# Regulator.net
KiCad netlist of a schematic drawn in Altium Designer
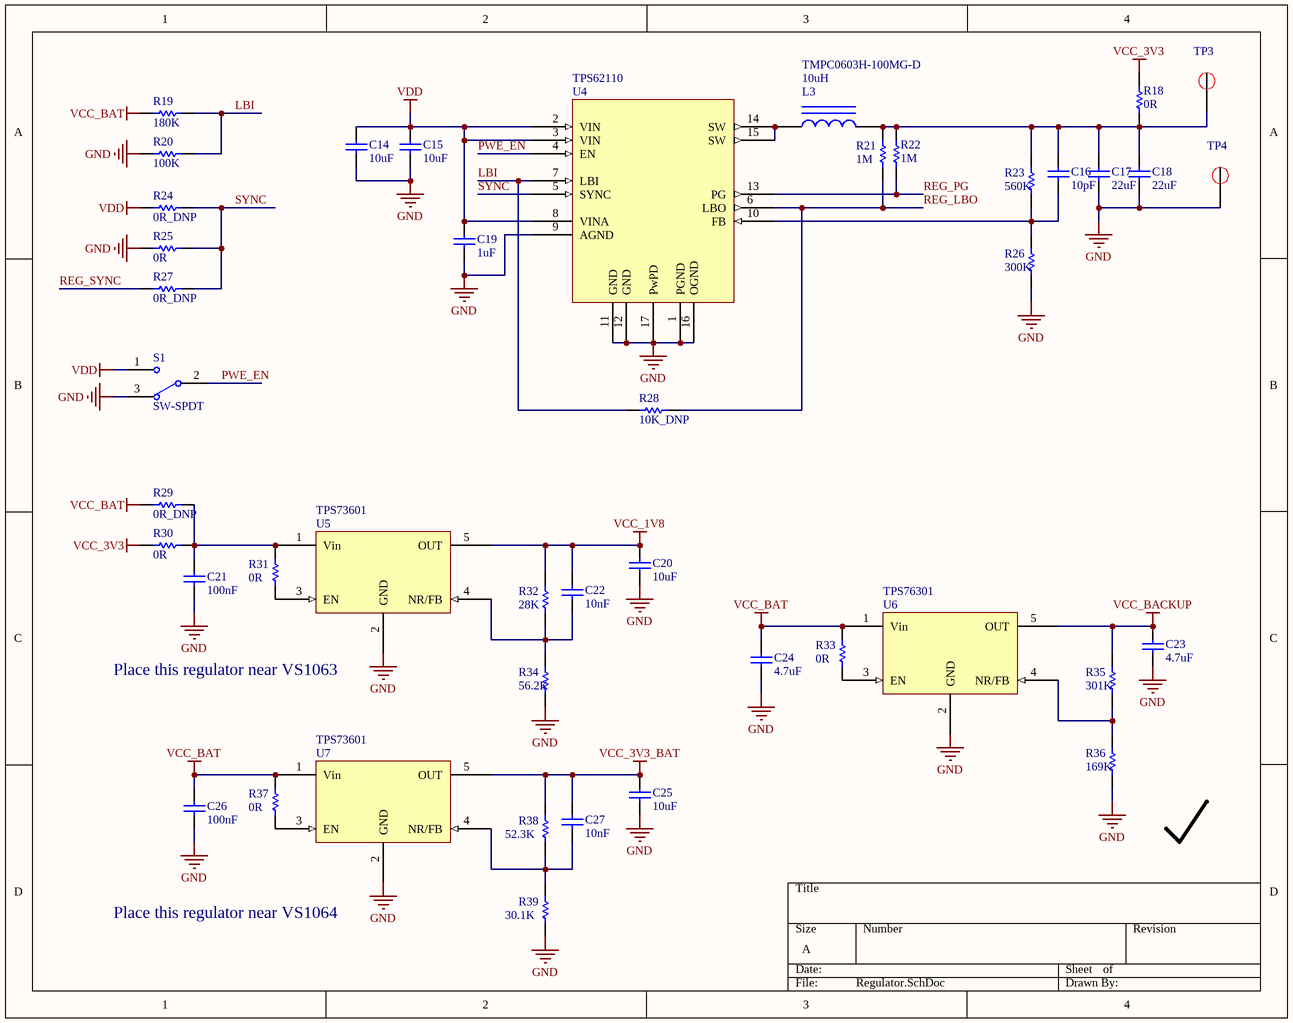
[diagram p0: Regulator.SchDoc]

(export (version "E")
  (design (tool "Eeschema 10.0.6"))
  (components
    (comp (ref "C14")
      (value "10uF")
      (footprint "C1206")
      (description "Capacitor (Semiconductor SIM Model)")
      (fields (field (name "Comment") "Cap Semi") (field (name "PUBLISHER") "Altium Limited"))
      (libsource (lib "Miscellaneous Devices") (part "Cap Semi"))
    )
    (comp (ref "C15")
      (value "10uF")
      (footprint "C1206")
      (description "Capacitor (Semiconductor SIM Model)")
      (fields (field (name "Comment") "Cap Semi") (field (name "PUBLISHER") "Altium Limited"))
      (libsource (lib "Miscellaneous Devices") (part "Cap Semi"))
    )
    (comp (ref "C16")
      (value "10pF")
      (footprint "0603PKG")
      (description "Capacitor (Semiconductor SIM Model)")
      (fields (field (name "Comment") "Cap Semi") (field (name "PUBLISHER") "Altium Limited"))
      (libsource (lib "Miscellaneous Devices") (part "Cap Semi"))
    )
    (comp (ref "C17")
      (value "22uF")
      (footprint "C1206")
      (description "Capacitor (Semiconductor SIM Model)")
      (fields (field (name "Comment") "Cap Semi") (field (name "PUBLISHER") "Altium Limited"))
      (libsource (lib "Miscellaneous Devices") (part "Cap Semi"))
    )
    (comp (ref "C18")
      (value "22uF")
      (footprint "C1206")
      (description "Capacitor (Semiconductor SIM Model)")
      (fields (field (name "Comment") "Cap Semi") (field (name "PUBLISHER") "Altium Limited"))
      (libsource (lib "Miscellaneous Devices") (part "Cap Semi"))
    )
    (comp (ref "C19")
      (value "1uF")
      (footprint "0603PKG")
      (description "Capacitor (Semiconductor SIM Model)")
      (fields (field (name "Comment") "Cap Semi") (field (name "PUBLISHER") "Altium Limited"))
      (libsource (lib "Miscellaneous Devices") (part "Cap Semi"))
    )
    (comp (ref "C20")
      (value "10uF")
      (footprint "0603PKG")
      (description "Capacitor (Semiconductor SIM Model)")
      (fields (field (name "Comment") "Cap Semi") (field (name "PUBLISHER") "Altium Limited"))
      (libsource (lib "Miscellaneous Devices") (part "Cap Semi"))
    )
    (comp (ref "C21")
      (value "100nF")
      (footprint "0603PKG")
      (description "Capacitor (Semiconductor SIM Model)")
      (fields (field (name "Comment") "Cap Semi") (field (name "PUBLISHER") "Altium Limited"))
      (libsource (lib "Miscellaneous Devices") (part "Cap Semi"))
    )
    (comp (ref "C22")
      (value "10nF")
      (footprint "0603PKG")
      (description "Capacitor (Semiconductor SIM Model)")
      (fields (field (name "Comment") "Cap Semi") (field (name "PUBLISHER") "Altium Limited"))
      (libsource (lib "Miscellaneous Devices") (part "Cap Semi"))
    )
    (comp (ref "C23")
      (value "4.7uF")
      (footprint "C0805")
      (description "Capacitor (Semiconductor SIM Model)")
      (fields (field (name "Comment") "Cap Semi") (field (name "PUBLISHER") "Altium Limited"))
      (libsource (lib "Miscellaneous Devices") (part "Cap Semi"))
    )
    (comp (ref "C24")
      (value "4.7uF")
      (footprint "C0805")
      (description "Capacitor (Semiconductor SIM Model)")
      (fields (field (name "Comment") "Cap Semi") (field (name "PUBLISHER") "Altium Limited"))
      (libsource (lib "Miscellaneous Devices") (part "Cap Semi"))
    )
    (comp (ref "C25")
      (value "10uF")
      (footprint "0603PKG")
      (description "Capacitor (Semiconductor SIM Model)")
      (fields (field (name "Comment") "Cap Semi") (field (name "PUBLISHER") "Altium Limited"))
      (libsource (lib "Miscellaneous Devices") (part "Cap Semi"))
    )
    (comp (ref "C26")
      (value "100nF")
      (footprint "0603PKG")
      (description "Capacitor (Semiconductor SIM Model)")
      (fields (field (name "Comment") "Cap Semi") (field (name "PUBLISHER") "Altium Limited"))
      (libsource (lib "Miscellaneous Devices") (part "Cap Semi"))
    )
    (comp (ref "C27")
      (value "10nF")
      (footprint "0603PKG")
      (description "Capacitor (Semiconductor SIM Model)")
      (fields (field (name "Comment") "Cap Semi") (field (name "PUBLISHER") "Altium Limited"))
      (libsource (lib "Miscellaneous Devices") (part "Cap Semi"))
    )
    (comp (ref "L3")
      (value "TMPC0603H-100MG-D")
      (footprint "CAPM3216X18N")
      (description "Magnetic-Core Inductor")
      (fields (field (name "ALTIUM_VALUE") "10uH") (field (name "PUBLISHER") "Altium Limited"))
      (libsource (lib "Miscellaneous Devices") (part "Inductor Iron"))
    )
    (comp (ref "R18")
      (value "0R")
      (footprint "C0805")
      (description "Resistor")
      (fields (field (name "Comment") "Res1") (field (name "PUBLISHER") "Altium Limited"))
      (libsource (lib "Miscellaneous Devices") (part "Res1"))
    )
    (comp (ref "R19")
      (value "180K")
      (footprint "0603PKG")
      (description "Resistor")
      (fields (field (name "Comment") "Res1") (field (name "PUBLISHER") "Altium Limited"))
      (libsource (lib "Miscellaneous Devices") (part "Res1"))
    )
    (comp (ref "R20")
      (value "100K")
      (footprint "0603PKG")
      (description "Resistor")
      (fields (field (name "Comment") "Res1") (field (name "PUBLISHER") "Altium Limited"))
      (libsource (lib "Miscellaneous Devices") (part "Res1"))
    )
    (comp (ref "R21")
      (value "1M")
      (footprint "0603PKG")
      (description "Resistor")
      (fields (field (name "Comment") "Res1") (field (name "PUBLISHER") "Altium Limited"))
      (libsource (lib "Miscellaneous Devices") (part "Res1"))
    )
    (comp (ref "R22")
      (value "1M")
      (footprint "0603PKG")
      (description "Resistor")
      (fields (field (name "Comment") "Res1") (field (name "PUBLISHER") "Altium Limited"))
      (libsource (lib "Miscellaneous Devices") (part "Res1"))
    )
    (comp (ref "R23")
      (value "560K")
      (footprint "0603PKG")
      (description "Resistor")
      (fields (field (name "Comment") "Res1") (field (name "PUBLISHER") "Altium Limited"))
      (libsource (lib "Miscellaneous Devices") (part "Res1"))
    )
    (comp (ref "R24")
      (value "0R_DNP")
      (footprint "0603PKG")
      (description "Resistor")
      (fields (field (name "Comment") "Res1") (field (name "PUBLISHER") "Altium Limited"))
      (libsource (lib "Miscellaneous Devices") (part "Res1"))
    )
    (comp (ref "R25")
      (value "0R")
      (footprint "0603PKG")
      (description "Resistor")
      (fields (field (name "Comment") "Res1") (field (name "PUBLISHER") "Altium Limited"))
      (libsource (lib "Miscellaneous Devices") (part "Res1"))
    )
    (comp (ref "R26")
      (value "300K")
      (footprint "0603PKG")
      (description "Resistor")
      (fields (field (name "Comment") "Res1") (field (name "PUBLISHER") "Altium Limited"))
      (libsource (lib "Miscellaneous Devices") (part "Res1"))
    )
    (comp (ref "R27")
      (value "0R_DNP")
      (footprint "0603PKG")
      (description "Resistor")
      (fields (field (name "Comment") "Res1") (field (name "PUBLISHER") "Altium Limited"))
      (libsource (lib "Miscellaneous Devices") (part "Res1"))
    )
    (comp (ref "R28")
      (value "10K_DNP")
      (footprint "0603PKG")
      (description "Resistor")
      (fields (field (name "Comment") "Res1") (field (name "PUBLISHER") "Altium Limited"))
      (libsource (lib "Miscellaneous Devices") (part "Res1"))
    )
    (comp (ref "R29")
      (value "0R_DNP")
      (footprint "0603PKG")
      (description "Resistor")
      (fields (field (name "Comment") "Res1") (field (name "PUBLISHER") "Altium Limited"))
      (libsource (lib "Miscellaneous Devices") (part "Res1"))
    )
    (comp (ref "R30")
      (value "0R")
      (footprint "0603PKG")
      (description "Resistor")
      (fields (field (name "Comment") "Res1") (field (name "PUBLISHER") "Altium Limited"))
      (libsource (lib "Miscellaneous Devices") (part "Res1"))
    )
    (comp (ref "R31")
      (value "0R")
      (footprint "0603PKG")
      (description "Resistor")
      (fields (field (name "Comment") "Res1") (field (name "PUBLISHER") "Altium Limited"))
      (libsource (lib "Miscellaneous Devices") (part "Res1"))
    )
    (comp (ref "R32")
      (value "28K")
      (footprint "0603PKG")
      (description "Resistor")
      (fields (field (name "Comment") "Res1") (field (name "PUBLISHER") "Altium Limited"))
      (libsource (lib "Miscellaneous Devices") (part "Res1"))
    )
    (comp (ref "R33")
      (value "0R")
      (footprint "0603PKG")
      (description "Resistor")
      (fields (field (name "Comment") "Res1") (field (name "PUBLISHER") "Altium Limited"))
      (libsource (lib "Miscellaneous Devices") (part "Res1"))
    )
    (comp (ref "R34")
      (value "56.2K")
      (footprint "0603PKG")
      (description "Resistor")
      (fields (field (name "Comment") "Res1") (field (name "PUBLISHER") "Altium Limited"))
      (libsource (lib "Miscellaneous Devices") (part "Res1"))
    )
    (comp (ref "R35")
      (value "301K")
      (footprint "0603PKG")
      (description "Resistor")
      (fields (field (name "Comment") "Res1") (field (name "PUBLISHER") "Altium Limited"))
      (libsource (lib "Miscellaneous Devices") (part "Res1"))
    )
    (comp (ref "R36")
      (value "169K")
      (footprint "0603PKG")
      (description "Resistor")
      (fields (field (name "Comment") "Res1") (field (name "PUBLISHER") "Altium Limited"))
      (libsource (lib "Miscellaneous Devices") (part "Res1"))
    )
    (comp (ref "R37")
      (value "0R")
      (footprint "0603PKG")
      (description "Resistor")
      (fields (field (name "Comment") "Res1") (field (name "PUBLISHER") "Altium Limited"))
      (libsource (lib "Miscellaneous Devices") (part "Res1"))
    )
    (comp (ref "R38")
      (value "52.3K")
      (footprint "0603PKG")
      (description "Resistor")
      (fields (field (name "Comment") "Res1") (field (name "PUBLISHER") "Altium Limited"))
      (libsource (lib "Miscellaneous Devices") (part "Res1"))
    )
    (comp (ref "R39")
      (value "30.1K")
      (footprint "0603PKG")
      (description "Resistor")
      (fields (field (name "Comment") "Res1") (field (name "PUBLISHER") "Altium Limited"))
      (libsource (lib "Miscellaneous Devices") (part "Res1"))
    )
    (comp (ref "S1")
      (value "SW-SPDT")
      (footprint "Slide switch")
      (description "SPDT Subminiature Toggle Switch, Right Angle Mounting, Vertical Actuation")
      (fields (field (name "PUBLISHER") "Altium Limited"))
      (libsource (lib "Miscellaneous Devices") (part "SW-SPDT"))
    )
    (comp (ref "TP3")
      (value "TP")
      (footprint "TP_15")
      (libsource (lib "Connector_IntLib") (part "Test Point"))
    )
    (comp (ref "TP4")
      (value "TP")
      (footprint "TP_15")
      (libsource (lib "Connector_IntLib") (part "Test Point"))
    )
    (comp (ref "U4")
      (value "TPS62110")
      (footprint "QFN16-4*4*0.65")
      (description "17-V, 1.5-A, SYNCHRONOUS STEP-DOWN CONVERTER")
      (fields (field (name "Comment") "Buck converter"))
      (libsource (lib "Connector_IntLib") (part "TPS62110"))
    )
    (comp (ref "U5")
      (value "TPS73601")
      (footprint "SOT23-5")
      (description "TPS736xx Cap-Free, NMOS, 400-mA Low-Dropout Regulator with Reverse Current  Protection")
      (libsource (lib "Connector_IntLib") (part "TPS73601"))
    )
    (comp (ref "U6")
      (value "TPS76301")
      (footprint "SOT23-5")
      (description "TPS763 Low-Power 150-mA Low-Dropout Linear Regulators")
      (libsource (lib "Connector_IntLib") (part "TPS76301"))
    )
    (comp (ref "U7")
      (value "TPS73601")
      (footprint "SOT23-5")
      (description "TPS736xx Cap-Free, NMOS, 400-mA Low-Dropout Regulator with Reverse Current  Protection")
      (libsource (lib "Connector_IntLib") (part "TPS73601"))
    )
  )
  (nets
    (net (code "1") (name "/LBI") (class "Default")
      (node (ref "R19") (pin "1") (pinfunction "1_1") (pintype "passive"))
      (node (ref "R20") (pin "1") (pinfunction "1_1") (pintype "passive"))
      (node (ref "R28") (pin "2") (pinfunction "2_2") (pintype "passive"))
      (node (ref "U4") (pin "7") (pinfunction "LBI_7") (pintype "input"))
    )
    (net (code "2") (name "/PWE_EN") (class "Default")
      (node (ref "S1") (pin "2") (pinfunction "2_2") (pintype "passive"))
      (node (ref "U4") (pin "4") (pinfunction "EN_4") (pintype "input"))
    )
    (net (code "3") (name "/REG_LBO") (class "Default")
      (node (ref "R21") (pin "1") (pinfunction "1_1") (pintype "passive"))
      (node (ref "R28") (pin "1") (pinfunction "1_1") (pintype "passive"))
      (node (ref "U4") (pin "6") (pinfunction "LBO_6") (pintype "output"))
    )
    (net (code "4") (name "/REG_PG") (class "Default")
      (node (ref "R22") (pin "2") (pinfunction "2_2") (pintype "passive"))
      (node (ref "U4") (pin "13") (pinfunction "PG_13") (pintype "output"))
    )
    (net (code "5") (name "/REG_SYNC") (class "Default")
      (node (ref "R27") (pin "2") (pinfunction "2_2") (pintype "passive"))
    )
    (net (code "6") (name "/SYNC") (class "Default")
      (node (ref "R24") (pin "1") (pinfunction "1_1") (pintype "passive"))
      (node (ref "R25") (pin "1") (pinfunction "1_1") (pintype "passive"))
      (node (ref "R27") (pin "1") (pinfunction "1_1") (pintype "passive"))
      (node (ref "U4") (pin "5") (pinfunction "SYNC_5") (pintype "input"))
    )
    (net (code "7") (name "GND") (class "Default")
      (node (ref "C14") (pin "2") (pinfunction "2_2") (pintype "passive"))
      (node (ref "C15") (pin "2") (pinfunction "2_2") (pintype "passive"))
      (node (ref "C17") (pin "2") (pinfunction "2_2") (pintype "passive"))
      (node (ref "C18") (pin "2") (pinfunction "2_2") (pintype "passive"))
      (node (ref "C19") (pin "2") (pinfunction "2_2") (pintype "passive"))
      (node (ref "C20") (pin "2") (pinfunction "2_2") (pintype "passive"))
      (node (ref "C21") (pin "2") (pinfunction "2_2") (pintype "passive"))
      (node (ref "C23") (pin "2") (pinfunction "2_2") (pintype "passive"))
      (node (ref "C24") (pin "2") (pinfunction "2_2") (pintype "passive"))
      (node (ref "C25") (pin "2") (pinfunction "2_2") (pintype "passive"))
      (node (ref "C26") (pin "2") (pinfunction "2_2") (pintype "passive"))
      (node (ref "R20") (pin "2") (pinfunction "2_2") (pintype "passive"))
      (node (ref "R25") (pin "2") (pinfunction "2_2") (pintype "passive"))
      (node (ref "R26") (pin "1") (pinfunction "1_1") (pintype "passive"))
      (node (ref "R34") (pin "1") (pinfunction "1_1") (pintype "passive"))
      (node (ref "R36") (pin "1") (pinfunction "1_1") (pintype "passive"))
      (node (ref "R39") (pin "1") (pinfunction "1_1") (pintype "passive"))
      (node (ref "S1") (pin "3") (pinfunction "3_3") (pintype "passive"))
      (node (ref "TP4") (pin "1") (pinfunction "1_1") (pintype "passive"))
      (node (ref "U4") (pin "1") (pinfunction "PGND_1") (pintype "power_in"))
      (node (ref "U4") (pin "11") (pinfunction "GND_11") (pintype "power_in"))
      (node (ref "U4") (pin "12") (pinfunction "GND_12") (pintype "power_in"))
      (node (ref "U4") (pin "16") (pinfunction "OGND_16") (pintype "power_in"))
      (node (ref "U4") (pin "17") (pinfunction "PwPD_17") (pintype "power_in"))
      (node (ref "U4") (pin "9") (pinfunction "AGND_9") (pintype "power_in"))
      (node (ref "U5") (pin "2") (pinfunction "GND_2") (pintype "power_in"))
      (node (ref "U6") (pin "2") (pinfunction "GND_2") (pintype "power_in"))
      (node (ref "U7") (pin "2") (pinfunction "GND_2") (pintype "power_in"))
    )
    (net (code "8") (name "Net-(C16-Pad1)") (class "Default")
      (node (ref "C16") (pin "1") (pinfunction "1_1") (pintype "passive"))
      (node (ref "C17") (pin "1") (pinfunction "1_1") (pintype "passive"))
      (node (ref "C18") (pin "1") (pinfunction "1_1") (pintype "passive"))
      (node (ref "L3") (pin "2") (pinfunction "2_2") (pintype "passive"))
      (node (ref "R18") (pin "2") (pinfunction "2_2") (pintype "passive"))
      (node (ref "R21") (pin "2") (pinfunction "2_2") (pintype "passive"))
      (node (ref "R22") (pin "1") (pinfunction "1_1") (pintype "passive"))
      (node (ref "R23") (pin "2") (pinfunction "2_2") (pintype "passive"))
      (node (ref "TP3") (pin "1") (pinfunction "1_1") (pintype "passive"))
    )
    (net (code "9") (name "Net-(L3-Pad1)") (class "Default")
      (node (ref "L3") (pin "1") (pinfunction "1_1") (pintype "passive"))
      (node (ref "U4") (pin "14") (pinfunction "SW_14") (pintype "output"))
      (node (ref "U4") (pin "15") (pinfunction "SW_15") (pintype "output"))
    )
    (net (code "10") (name "Net-(U4-FB)") (class "Default")
      (node (ref "C16") (pin "2") (pinfunction "2_2") (pintype "passive"))
      (node (ref "R23") (pin "1") (pinfunction "1_1") (pintype "passive"))
      (node (ref "R26") (pin "2") (pinfunction "2_2") (pintype "passive"))
      (node (ref "U4") (pin "10") (pinfunction "FB_10") (pintype "input"))
    )
    (net (code "11") (name "Net-(U5-EN)") (class "Default")
      (node (ref "R31") (pin "1") (pinfunction "1_1") (pintype "passive"))
      (node (ref "U5") (pin "3") (pinfunction "EN_3") (pintype "input"))
    )
    (net (code "12") (name "Net-(U5-NR{slash}FB)") (class "Default")
      (node (ref "C22") (pin "2") (pinfunction "2_2") (pintype "passive"))
      (node (ref "R32") (pin "1") (pinfunction "1_1") (pintype "passive"))
      (node (ref "R34") (pin "2") (pinfunction "2_2") (pintype "passive"))
      (node (ref "U5") (pin "4") (pinfunction "NR/FB_4") (pintype "input"))
    )
    (net (code "13") (name "Net-(U5-Vin)") (class "Default")
      (node (ref "C21") (pin "1") (pinfunction "1_1") (pintype "passive"))
      (node (ref "R29") (pin "1") (pinfunction "1_1") (pintype "passive"))
      (node (ref "R30") (pin "1") (pinfunction "1_1") (pintype "passive"))
      (node (ref "R31") (pin "2") (pinfunction "2_2") (pintype "passive"))
      (node (ref "U5") (pin "1") (pinfunction "Vin_1") (pintype "power_in"))
    )
    (net (code "14") (name "Net-(U6-EN)") (class "Default")
      (node (ref "R33") (pin "1") (pinfunction "1_1") (pintype "passive"))
      (node (ref "U6") (pin "3") (pinfunction "EN_3") (pintype "input"))
    )
    (net (code "15") (name "Net-(U6-NR{slash}FB)") (class "Default")
      (node (ref "R35") (pin "1") (pinfunction "1_1") (pintype "passive"))
      (node (ref "R36") (pin "2") (pinfunction "2_2") (pintype "passive"))
      (node (ref "U6") (pin "4") (pinfunction "NR/FB_4") (pintype "input"))
    )
    (net (code "16") (name "Net-(U7-EN)") (class "Default")
      (node (ref "R37") (pin "1") (pinfunction "1_1") (pintype "passive"))
      (node (ref "U7") (pin "3") (pinfunction "EN_3") (pintype "input"))
    )
    (net (code "17") (name "Net-(U7-NR{slash}FB)") (class "Default")
      (node (ref "C27") (pin "2") (pinfunction "2_2") (pintype "passive"))
      (node (ref "R38") (pin "1") (pinfunction "1_1") (pintype "passive"))
      (node (ref "R39") (pin "2") (pinfunction "2_2") (pintype "passive"))
      (node (ref "U7") (pin "4") (pinfunction "NR/FB_4") (pintype "input"))
    )
    (net (code "18") (name "VCC_1V8") (class "Default")
      (node (ref "C20") (pin "1") (pinfunction "1_1") (pintype "passive"))
      (node (ref "C22") (pin "1") (pinfunction "1_1") (pintype "passive"))
      (node (ref "R32") (pin "2") (pinfunction "2_2") (pintype "passive"))
      (node (ref "U5") (pin "5") (pinfunction "OUT_5") (pintype "power_in"))
    )
    (net (code "19") (name "VCC_3V3") (class "Default")
      (node (ref "R18") (pin "1") (pinfunction "1_1") (pintype "passive"))
      (node (ref "R30") (pin "2") (pinfunction "2_2") (pintype "passive"))
    )
    (net (code "20") (name "VCC_3V3_BAT") (class "Default")
      (node (ref "C25") (pin "1") (pinfunction "1_1") (pintype "passive"))
      (node (ref "C27") (pin "1") (pinfunction "1_1") (pintype "passive"))
      (node (ref "R38") (pin "2") (pinfunction "2_2") (pintype "passive"))
      (node (ref "U7") (pin "5") (pinfunction "OUT_5") (pintype "power_in"))
    )
    (net (code "21") (name "VCC_BACKUP") (class "Default")
      (node (ref "C23") (pin "1") (pinfunction "1_1") (pintype "passive"))
      (node (ref "R35") (pin "2") (pinfunction "2_2") (pintype "passive"))
      (node (ref "U6") (pin "5") (pinfunction "OUT_5") (pintype "power_in"))
    )
    (net (code "22") (name "VCC_BAT") (class "Default")
      (node (ref "C24") (pin "1") (pinfunction "1_1") (pintype "passive"))
      (node (ref "C26") (pin "1") (pinfunction "1_1") (pintype "passive"))
      (node (ref "R19") (pin "2") (pinfunction "2_2") (pintype "passive"))
      (node (ref "R29") (pin "2") (pinfunction "2_2") (pintype "passive"))
      (node (ref "R33") (pin "2") (pinfunction "2_2") (pintype "passive"))
      (node (ref "R37") (pin "2") (pinfunction "2_2") (pintype "passive"))
      (node (ref "U6") (pin "1") (pinfunction "Vin_1") (pintype "power_in"))
      (node (ref "U7") (pin "1") (pinfunction "Vin_1") (pintype "power_in"))
    )
    (net (code "23") (name "VDD") (class "Default")
      (node (ref "C14") (pin "1") (pinfunction "1_1") (pintype "passive"))
      (node (ref "C15") (pin "1") (pinfunction "1_1") (pintype "passive"))
      (node (ref "C19") (pin "1") (pinfunction "1_1") (pintype "passive"))
      (node (ref "R24") (pin "2") (pinfunction "2_2") (pintype "passive"))
      (node (ref "S1") (pin "1") (pinfunction "1_1") (pintype "passive"))
      (node (ref "U4") (pin "2") (pinfunction "VIN_2") (pintype "input"))
      (node (ref "U4") (pin "3") (pinfunction "VIN_3") (pintype "input"))
      (node (ref "U4") (pin "8") (pinfunction "VINA_8") (pintype "power_in"))
    )
  )
)
